# AnalogInputs.net
KiCad netlist of a schematic drawn in Altium Designer
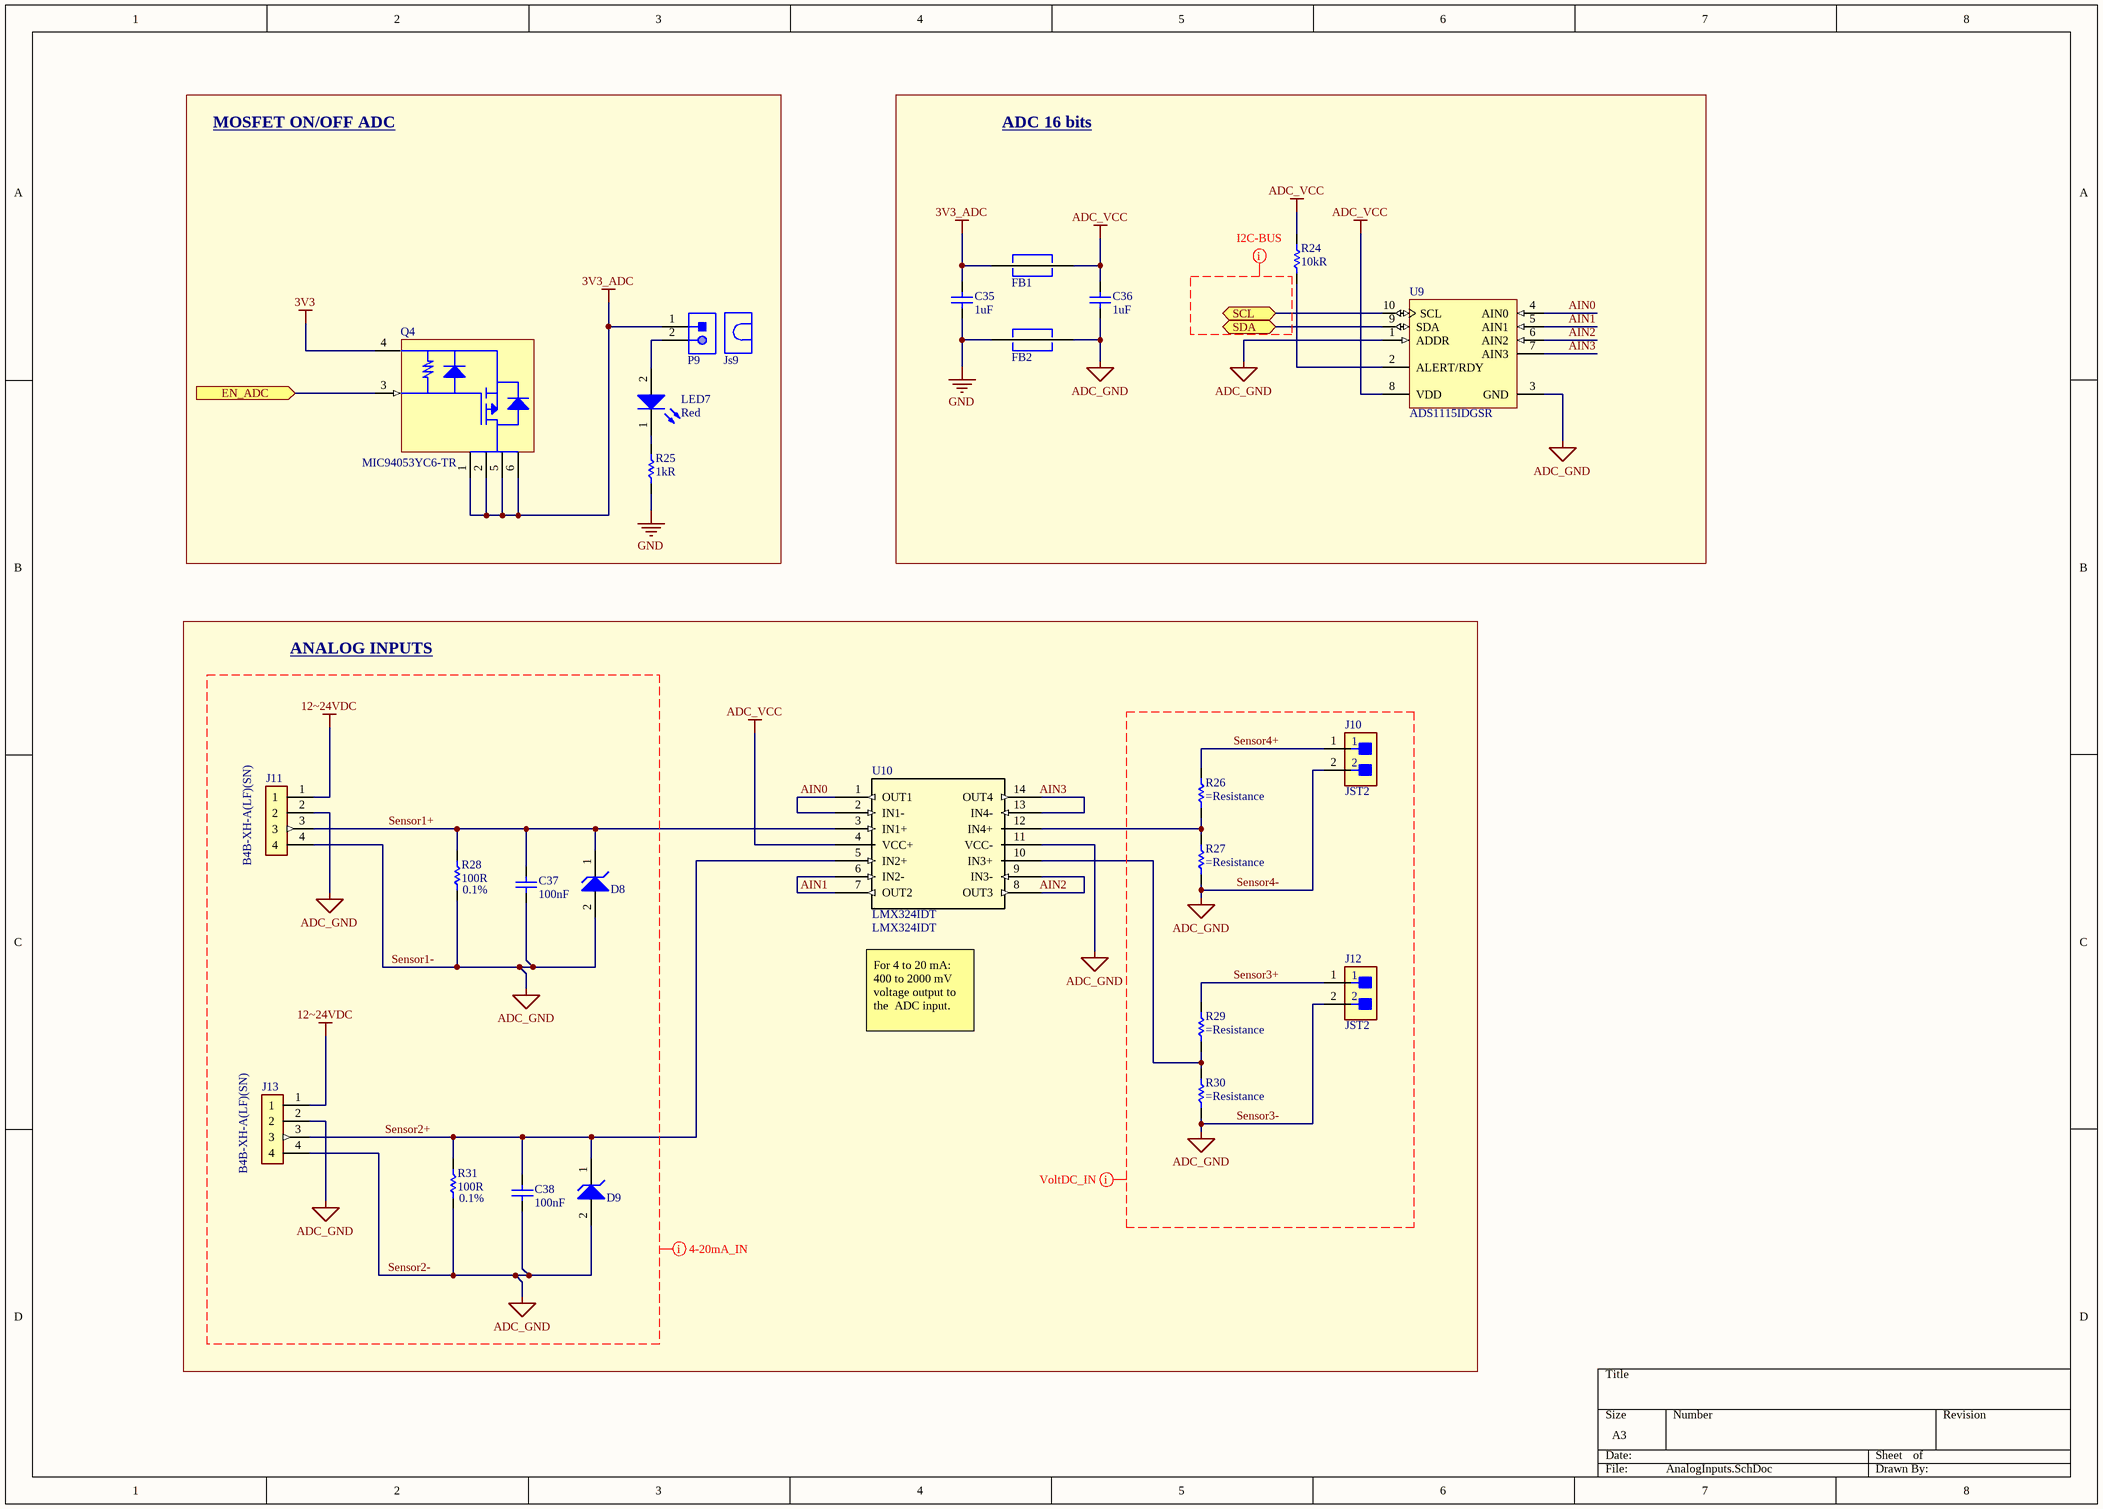
[diagram p0: AnalogInputs.SchDoc]

(export (version "E")
  (design (tool "Eeschema 10.0.6"))
  (components
    (comp (ref "C35")
      (value "1uF")
      (footprint "Cap 0805 (2012 Metric)")
      (description "Ceramic capacitor SMD-0805 1000nF /16V X7R# K +-10%, Samsung, RoHS/3000pcs/")
      (fields
        (field (name "MANUFACTURER") "Samsung")
        (field (name "MANUFACTURER PART NUMBER") "CL21B105KOFNNNG")
      )
      (libsource (lib "Daniel_Integrated_Library") (part "Capacitor"))
    )
    (comp (ref "C36")
      (value "1uF")
      (footprint "Cap 0805 (2012 Metric)")
      (description "Ceramic capacitor SMD-0805 1000nF /16V X7R# K +-10%, Samsung, RoHS/3000pcs/")
      (fields
        (field (name "MANUFACTURER") "Samsung")
        (field (name "MANUFACTURER PART NUMBER") "CL21B105KOFNNNG")
      )
      (libsource (lib "Daniel_Integrated_Library") (part "Capacitor"))
    )
    (comp (ref "C37")
      (value "100nF")
      (footprint "Cap 0805 (2012 Metric)")
      (fields
        (field (name "MANUFACTURER") "Yageo")
        (field (name "MANUFACTURER PART NUMBER") "CC0805ZRY5V9BB104")
        (field (name "TOLERANCE") "80%")
      )
      (libsource (lib "Daniel_Integrated_Library") (part "Capacitor"))
    )
    (comp (ref "C38")
      (value "100nF")
      (footprint "Cap 0805 (2012 Metric)")
      (fields
        (field (name "MANUFACTURER") "Yageo")
        (field (name "MANUFACTURER PART NUMBER") "CC0805ZRY5V9BB104")
        (field (name "TOLERANCE") "80%")
      )
      (libsource (lib "Daniel_Integrated_Library") (part "Capacitor"))
    )
    (comp (ref "D8")
      (value "Diode")
      (footprint "Diode SOD123")
      (description "DIODE GEN PURP 75V 150MA 0603")
      (fields
        (field (name "MANUFACTURER") "Taiwan Semiconductor")
        (field (name "MANUFACTURER PART NUMBER") "TS4148CRZG")
      )
      (libsource (lib "Daniel_Integrated_Library") (part "Diode"))
    )
    (comp (ref "D9")
      (value "Diode")
      (footprint "Diode SOD123")
      (description "DIODE GEN PURP 75V 150MA 0603")
      (fields
        (field (name "MANUFACTURER") "Taiwan Semiconductor")
        (field (name "MANUFACTURER PART NUMBER") "TS4148CRZG")
      )
      (libsource (lib "Daniel_Integrated_Library") (part "Diode"))
    )
    (comp (ref "FB1")
      (value "Ferrite Bead")
      (footprint "Ferrite Bead 0805 (2012 Metric)")
      (description "1 kOhms @ 100MHz 1 Power Line Ferrite Bead 0805 (2012 Metric) 1.5A 150mOhm")
      (fields
        (field (name "MANUFACTURER") "TDK")
        (field (name "MANUFACTURER PART NUMBER") "MPZ2012S102AT000")
      )
      (libsource (lib "Daniel_Integrated_Library") (part "Ferrite Bead"))
    )
    (comp (ref "FB2")
      (value "Ferrite Bead")
      (footprint "Ferrite Bead 0805 (2012 Metric)")
      (description "1 kOhms @ 100MHz 1 Power Line Ferrite Bead 0805 (2012 Metric) 1.5A 150mOhm")
      (fields
        (field (name "MANUFACTURER") "TDK")
        (field (name "MANUFACTURER PART NUMBER") "MPZ2012S102AT000")
      )
      (libsource (lib "Daniel_Integrated_Library") (part "Ferrite Bead"))
    )
    (comp (ref "J10")
      (value "JST2")
      (footprint "JST2")
      (description "Conn Shrouded Header (4 Sides) HDR 2 POS 2.5mm Solder ST Thru-Hole Box")
      (fields
        (field (name "MANUFACTURER") "JST")
        (field (name "MANUFACTURER PART NUMBER") "B2B-XH-A(LF)(SN)")
      )
      (libsource (lib "stratos") (part "JST2"))
    )
    (comp (ref "J11")
      (value "B4B-XH-A(LF)(SN)")
      (footprint "B4B-XH-A(LF)(SN)")
      (fields (field (name "MANUFACTURER") "JST"))
      (libsource (lib "stratos") (part "B4B-XH-A(LF)(SN)"))
    )
    (comp (ref "J12")
      (value "JST2")
      (footprint "JST2")
      (description "Conn Shrouded Header (4 Sides) HDR 2 POS 2.5mm Solder ST Thru-Hole Box")
      (fields
        (field (name "MANUFACTURER") "JST")
        (field (name "MANUFACTURER PART NUMBER") "B2B-XH-A(LF)(SN)")
      )
      (libsource (lib "stratos") (part "JST2"))
    )
    (comp (ref "J13")
      (value "B4B-XH-A(LF)(SN)")
      (footprint "B4B-XH-A(LF)(SN)")
      (fields (field (name "MANUFACTURER") "JST"))
      (libsource (lib "stratos") (part "B4B-XH-A(LF)(SN)"))
    )
    (comp (ref "Js9")
      (value "Jumper (2x1)")
      (footprint "Header JMP 2x1")
      (description "2 (1 x 2) Position Shunt Connector Black Open Top 0.100\" (2.54mm) Gold")
      (fields
        (field (name "MANUFACTURER") "Sullins")
        (field (name "MANUFACTURER PART NUMBER") "QPC02SXGN-RC")
      )
      (libsource (lib "Daniel_Integrated_Library") (part "Jumper (2x1)"))
    )
    (comp (ref "LED7")
      (value "Red")
      (footprint "LED 0805(2012 METRIC)")
      (description "SMD LED red 2.4 V 0805, 150080RS75000, Würth Elektronik")
      (fields
        (field (name "MANUFACTURER") "Wurth Electronics")
        (field (name "MANUFACTURER PART NUMBER") "150080RS75000")
      )
      (libsource (lib "Daniel_Integrated_Library") (part "LED"))
    )
    (comp (ref "P9")
      (value "Header 2x1")
      (footprint "Header 2x1")
      (description "Connector Header Through Hole 2 position 0.100\" (2.54mm)")
      (fields
        (field (name "MANUFACTURER") "Amphenol FCI")
        (field (name "MANUFACTURER PART NUMBER") "68001-402HLF")
      )
      (libsource (lib "Daniel_Integrated_Library") (part "Header 2x1"))
    )
    (comp (ref "Q4")
      (value "MIC94053YC6-TR")
      (footprint "SC-70-6")
      (description "P-Channel 6V 2A (Ta) 270mW (Ta) Surface Mount SC-70-6")
      (fields (field (name "MANUFACTURER") "Microchip"))
      (libsource (lib "Daniel_Integrated_Library") (part "TransistorMosfet(Load)"))
    )
    (comp (ref "R24")
      (value "10kR")
      (footprint "Res 0805 (2012 Metric)")
      (description "RES 10K OHM 1% 1/4W 0805")
      (fields
        (field (name "MANUFACTURER") "Stackpole Electronics")
        (field (name "MANUFACTURER PART NUMBER") "RNCP0805FTD10K0")
      )
      (libsource (lib "Daniel_Integrated_Library") (part "Resistor"))
    )
    (comp (ref "R25")
      (value "1kR")
      (footprint "Res 0805 (2012 Metric)")
      (description "RES 1K OHM 1% 1/4W 0805")
      (fields
        (field (name "MANUFACTURER") "Stackpole Electronics")
        (field (name "MANUFACTURER PART NUMBER") "RNCP0805FTD1K00")
      )
      (libsource (lib "Daniel_Integrated_Library") (part "Resistor"))
    )
    (comp (ref "R26")
      (value "~")
      (footprint "Res 0805 (2012 Metric)")
      (libsource (lib "Daniel_Integrated_Library") (part "Resistor"))
    )
    (comp (ref "R27")
      (value "~")
      (footprint "Res 0805 (2012 Metric)")
      (libsource (lib "Daniel_Integrated_Library") (part "Resistor"))
    )
    (comp (ref "R28")
      (value "100R")
      (footprint "Res 1206 (3216 Metric)")
      (description "RES 100 OHM 0.40W 0.1% 1206")
      (fields
        (field (name "MANUFACTURER") "Vishay Dale Thin Film")
        (field (name "MANUFACTURER PART NUMBER") "PTN1206E1000BST1")
        (field (name "TOLERANCE") "0.1%")
      )
      (libsource (lib "Daniel_Integrated_Library") (part "Resistor"))
    )
    (comp (ref "R29")
      (value "~")
      (footprint "Res 0805 (2012 Metric)")
      (libsource (lib "Daniel_Integrated_Library") (part "Resistor"))
    )
    (comp (ref "R30")
      (value "~")
      (footprint "Res 0805 (2012 Metric)")
      (libsource (lib "Daniel_Integrated_Library") (part "Resistor"))
    )
    (comp (ref "R31")
      (value "100R")
      (footprint "Res 1206 (3216 Metric)")
      (description "RES 100 OHM 0.40W 0.1% 1206")
      (fields
        (field (name "MANUFACTURER") "Vishay Dale Thin Film")
        (field (name "MANUFACTURER PART NUMBER") "PTN1206E1000BST1")
        (field (name "TOLERANCE") "0.1%")
      )
      (libsource (lib "Daniel_Integrated_Library") (part "Resistor"))
    )
    (comp (ref "U9")
      (value "ADS1115IDGSR")
      (footprint "10-VSSOP")
      (description "TEXAS INSTRUMENTS - ADS1115IDGSR - ADC, 16BIT, 860SPS, I2C, VSSOP-10")
      (fields (field (name "MANUFACTURER") "Texas Instruments"))
      (libsource (lib "Daniel_Integrated_Library") (part "ADS1115IDGSR"))
    )
    (comp (ref "U10")
      (value "LMX324IDT")
      (footprint "LMX324IDT")
      (description "OP Amp Quad GP R-R O/P 5.5V 14-Pin SOIC T/R")
      (fields
        (field (name "MANUFACTURER") "STMicroelectronics")
        (field (name "MANUFACTURER PART NUMBER") "LMX324IDT")
      )
      (libsource (lib "stratos") (part "LMX324IDT"))
    )
  )
  (nets
    (net (code "1") (name "/AIN0") (class "Default")
      (node (ref "U10") (pin "1") (pinfunction "OUT1_1") (pintype "output"))
      (node (ref "U10") (pin "2") (pinfunction "IN1-_2") (pintype "input"))
      (node (ref "U9") (pin "4") (pinfunction "AIN0_4") (pintype "input"))
    )
    (net (code "2") (name "/AIN1") (class "Default")
      (node (ref "U10") (pin "6") (pinfunction "IN2-_6") (pintype "input"))
      (node (ref "U10") (pin "7") (pinfunction "OUT2_7") (pintype "output"))
      (node (ref "U9") (pin "5") (pinfunction "AIN1_5") (pintype "input"))
    )
    (net (code "3") (name "/AIN2") (class "Default")
      (node (ref "U10") (pin "8") (pinfunction "OUT3_8") (pintype "output"))
      (node (ref "U10") (pin "9") (pinfunction "IN3-_9") (pintype "input"))
      (node (ref "U9") (pin "6") (pinfunction "AIN2_6") (pintype "input"))
    )
    (net (code "4") (name "/AIN3") (class "Default")
      (node (ref "U10") (pin "13") (pinfunction "IN4-_13") (pintype "input"))
      (node (ref "U10") (pin "14") (pinfunction "OUT4_14") (pintype "output"))
      (node (ref "U9") (pin "7") (pinfunction "AIN3_7") (pintype "passive"))
    )
    (net (code "5") (name "/EN_ADC") (class "Default")
      (node (ref "Q4") (pin "3") (pinfunction "G_3") (pintype "input"))
    )
    (net (code "6") (name "/SCL") (class "Default")
      (node (ref "U9") (pin "10") (pinfunction "SCL_10") (pintype "bidirectional"))
    )
    (net (code "7") (name "/SDA") (class "Default")
      (node (ref "U9") (pin "9") (pinfunction "SDA_9") (pintype "bidirectional"))
    )
    (net (code "8") (name "/Sensor1+") (class "Default")
      (node (ref "C37") (pin "1") (pinfunction "1_1") (pintype "passive"))
      (node (ref "D8") (pin "1") (pinfunction "K_1") (pintype "passive"))
      (node (ref "J11") (pin "3") (pinfunction "3_3") (pintype "output"))
      (node (ref "R28") (pin "1") (pinfunction "1_1") (pintype "passive"))
      (node (ref "U10") (pin "3") (pinfunction "IN1+_3") (pintype "input"))
    )
    (net (code "9") (name "/Sensor2+") (class "Default")
      (node (ref "C38") (pin "1") (pinfunction "1_1") (pintype "passive"))
      (node (ref "D9") (pin "1") (pinfunction "K_1") (pintype "passive"))
      (node (ref "J13") (pin "3") (pinfunction "3_3") (pintype "output"))
      (node (ref "R31") (pin "1") (pinfunction "1_1") (pintype "passive"))
      (node (ref "U10") (pin "5") (pinfunction "IN2+_5") (pintype "input"))
    )
    (net (code "10") (name "/Sensor3+") (class "Default")
      (node (ref "J12") (pin "1") (pinfunction "1_1") (pintype "passive"))
      (node (ref "R29") (pin "1") (pinfunction "1_1") (pintype "passive"))
    )
    (net (code "11") (name "/Sensor4+") (class "Default")
      (node (ref "J10") (pin "1") (pinfunction "1_1") (pintype "passive"))
      (node (ref "R26") (pin "1") (pinfunction "1_1") (pintype "passive"))
    )
    (net (code "12") (name "3V3") (class "Default")
      (node (ref "Q4") (pin "4") (pinfunction "S_4") (pintype "passive"))
    )
    (net (code "13") (name "3V3_ADC") (class "Default")
      (node (ref "C35") (pin "1") (pinfunction "1_1") (pintype "passive"))
      (node (ref "FB1") (pin "1") (pinfunction "1_1") (pintype "passive"))
      (node (ref "P9") (pin "1") (pinfunction "1_1") (pintype "passive"))
      (node (ref "Q4") (pin "1") (pinfunction "D_1") (pintype "passive"))
      (node (ref "Q4") (pin "2") (pinfunction "D_2") (pintype "passive"))
      (node (ref "Q4") (pin "5") (pinfunction "D_5") (pintype "passive"))
      (node (ref "Q4") (pin "6") (pinfunction "D_6") (pintype "passive"))
    )
    (net (code "14") (name "12~24VDC") (class "Default")
      (node (ref "J11") (pin "1") (pinfunction "1_1") (pintype "passive"))
      (node (ref "J13") (pin "1") (pinfunction "1_1") (pintype "passive"))
    )
    (net (code "15") (name "ADC_GND") (class "Default")
      (node (ref "C36") (pin "2") (pinfunction "2_2") (pintype "passive"))
      (node (ref "C37") (pin "2") (pinfunction "2_2") (pintype "passive"))
      (node (ref "C38") (pin "2") (pinfunction "2_2") (pintype "passive"))
      (node (ref "D8") (pin "2") (pinfunction "A_2") (pintype "passive"))
      (node (ref "D9") (pin "2") (pinfunction "A_2") (pintype "passive"))
      (node (ref "FB2") (pin "1") (pinfunction "1_1") (pintype "passive"))
      (node (ref "J10") (pin "2") (pinfunction "2_2") (pintype "passive"))
      (node (ref "J11") (pin "2") (pinfunction "2_2") (pintype "passive"))
      (node (ref "J11") (pin "4") (pinfunction "4_4") (pintype "passive"))
      (node (ref "J12") (pin "2") (pinfunction "2_2") (pintype "passive"))
      (node (ref "J13") (pin "2") (pinfunction "2_2") (pintype "passive"))
      (node (ref "J13") (pin "4") (pinfunction "4_4") (pintype "passive"))
      (node (ref "R27") (pin "2") (pinfunction "2_2") (pintype "passive"))
      (node (ref "R28") (pin "2") (pinfunction "2_2") (pintype "passive"))
      (node (ref "R30") (pin "2") (pinfunction "2_2") (pintype "passive"))
      (node (ref "R31") (pin "2") (pinfunction "2_2") (pintype "passive"))
      (node (ref "U10") (pin "11") (pinfunction "VCC-_11") (pintype "power_in"))
      (node (ref "U9") (pin "1") (pinfunction "ADDR_1") (pintype "input"))
      (node (ref "U9") (pin "3") (pinfunction "GND_3") (pintype "power_in"))
    )
    (net (code "16") (name "ADC_VCC") (class "Default")
      (node (ref "C36") (pin "1") (pinfunction "1_1") (pintype "passive"))
      (node (ref "FB1") (pin "2") (pinfunction "2_2") (pintype "passive"))
      (node (ref "R24") (pin "1") (pinfunction "1_1") (pintype "passive"))
      (node (ref "U10") (pin "4") (pinfunction "VCC+_4") (pintype "power_in"))
      (node (ref "U9") (pin "8") (pinfunction "VDD_8") (pintype "power_in"))
    )
    (net (code "17") (name "GND") (class "Default")
      (node (ref "C35") (pin "2") (pinfunction "2_2") (pintype "passive"))
      (node (ref "FB2") (pin "2") (pinfunction "2_2") (pintype "passive"))
      (node (ref "R25") (pin "2") (pinfunction "2_2") (pintype "passive"))
    )
    (net (code "18") (name "Net-(LED7-A)") (class "Default")
      (node (ref "LED7") (pin "2") (pinfunction "A_2") (pintype "passive"))
      (node (ref "P9") (pin "2") (pinfunction "2_2") (pintype "passive"))
    )
    (net (code "19") (name "Net-(LED7-K)") (class "Default")
      (node (ref "LED7") (pin "1") (pinfunction "K_1") (pintype "passive"))
      (node (ref "R25") (pin "1") (pinfunction "1_1") (pintype "passive"))
    )
    (net (code "20") (name "Net-(U9-ALERT{slash}RDY)") (class "Default")
      (node (ref "R24") (pin "2") (pinfunction "2_2") (pintype "passive"))
      (node (ref "U9") (pin "2") (pinfunction "ALERT/RDY_2") (pintype "open_collector"))
    )
    (net (code "21") (name "Net-(U10-IN3+)") (class "Default")
      (node (ref "R29") (pin "2") (pinfunction "2_2") (pintype "passive"))
      (node (ref "R30") (pin "1") (pinfunction "1_1") (pintype "passive"))
      (node (ref "U10") (pin "10") (pinfunction "IN3+_10") (pintype "passive"))
    )
    (net (code "22") (name "Net-(U10-IN4+)") (class "Default")
      (node (ref "R26") (pin "2") (pinfunction "2_2") (pintype "passive"))
      (node (ref "R27") (pin "1") (pinfunction "1_1") (pintype "passive"))
      (node (ref "U10") (pin "12") (pinfunction "IN4+_12") (pintype "passive"))
    )
  )
)
